# I-V_E9A_05_6231.net
KiCad netlist of a schematic drawn in Altium Designer
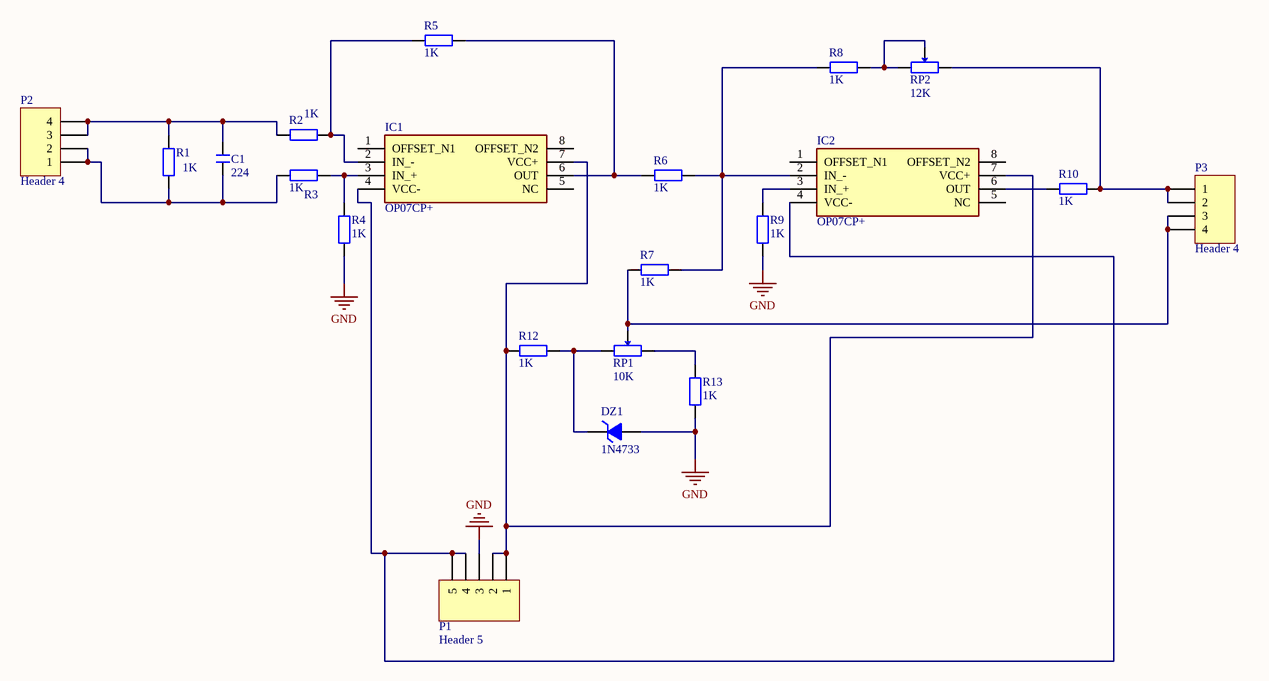
[diagram p0: I-V E9A_05_6231.SchDoc]

(export (version "E")
  (design (tool "Eeschema 10.0.6"))
  (components
    (comp (ref "C1")
      (value "224")
      (footprint "MLCC5.08-A")
      (description "独石电容")
      (fields (field (name "版权归属") "源创客"))
      (libsource (lib "3.1   - 电阻-电容-电感") (part "C-MLCC"))
    )
    (comp (ref "DZ1")
      (value "1N4733")
      (footprint "DO-41")
      (description "5.1V/1W稳压管")
      (fields (field (name "版权归属") "源创客"))
      (libsource (lib "8.1   - 二极管-整流桥") (part "1N4733"))
    )
    (comp (ref "IC1")
      (value "OP07CP+")
      (footprint "SamacSys:DIP794W53P254L959H508Q8N")
      (description "Integrated Circuit")
      (libsource (lib "*") (part "OP07CP+"))
    )
    (comp (ref "IC2")
      (value "OP07CP+")
      (footprint "SamacSys:DIP794W53P254L959H508Q8N")
      (description "Integrated Circuit")
      (libsource (lib "*") (part "OP07CP+"))
    )
    (comp (ref "P1")
      (value "Header 5")
      (footprint "POWER PLUG5")
      (description "Header, 5-Pin")
      (fields (field (name "PUBLISHER") "Altium Limited"))
      (libsource (lib "Miscellaneous Connectors") (part "Header 5"))
    )
    (comp (ref "P2")
      (value "Header 4")
      (footprint "HDR1X4")
      (description "Header, 4-Pin")
      (fields (field (name "PUBLISHER") "Altium Limited"))
      (libsource (lib "") (part "Header 4_1"))
    )
    (comp (ref "P3")
      (value "Header 4")
      (footprint "HDR1X4")
      (description "Header, 4-Pin")
      (fields (field (name "PUBLISHER") "Altium Limited"))
      (libsource (lib "Miscellaneous Connectors") (part "Header 4"))
    )
    (comp (ref "R1")
      (value "1K")
      (footprint "RS 1/4W")
      (description "直插色环电阻")
      (fields (field (name "版权归属") "源创客"))
      (libsource (lib "3.1   - 电阻-电容-电感") (part "R-CRR"))
    )
    (comp (ref "R2")
      (value "1K")
      (footprint "RS 1/4W")
      (description "直插色环电阻")
      (fields (field (name "版权归属") "源创客"))
      (libsource (lib "3.1   - 电阻-电容-电感") (part "R-CRR"))
    )
    (comp (ref "R3")
      (value "1K")
      (footprint "RS 1/4W")
      (description "直插色环电阻")
      (fields (field (name "版权归属") "源创客"))
      (libsource (lib "3.1   - 电阻-电容-电感") (part "R-CRR"))
    )
    (comp (ref "R4")
      (value "1K")
      (footprint "RS 1/4W")
      (description "直插色环电阻")
      (fields (field (name "版权归属") "源创客"))
      (libsource (lib "3.1   - 电阻-电容-电感") (part "R-CRR"))
    )
    (comp (ref "R5")
      (value "1K")
      (footprint "RS 1/4W")
      (description "直插色环电阻")
      (fields (field (name "版权归属") "源创客"))
      (libsource (lib "3.1   - 电阻-电容-电感") (part "R-CRR"))
    )
    (comp (ref "R6")
      (value "1K")
      (footprint "RS 1/4W")
      (description "直插色环电阻")
      (fields (field (name "版权归属") "源创客"))
      (libsource (lib "3.1   - 电阻-电容-电感") (part "R-CRR"))
    )
    (comp (ref "R7")
      (value "1K")
      (footprint "RS 1/4W")
      (description "直插色环电阻")
      (fields (field (name "版权归属") "源创客"))
      (libsource (lib "3.1   - 电阻-电容-电感") (part "R-CRR"))
    )
    (comp (ref "R8")
      (value "1K")
      (footprint "RS 1/4W")
      (description "直插色环电阻")
      (fields (field (name "版权归属") "源创客"))
      (libsource (lib "3.1   - 电阻-电容-电感") (part "R-CRR"))
    )
    (comp (ref "R9")
      (value "1K")
      (footprint "RS 1/4W")
      (description "直插色环电阻")
      (fields (field (name "版权归属") "源创客"))
      (libsource (lib "3.1   - 电阻-电容-电感") (part "R-CRR"))
    )
    (comp (ref "R10")
      (value "1K")
      (footprint "RS 1/4W")
      (description "直插色环电阻")
      (fields (field (name "版权归属") "源创客"))
      (libsource (lib "3.1   - 电阻-电容-电感") (part "R-CRR"))
    )
    (comp (ref "R12")
      (value "1K")
      (footprint "RS 1/4W")
      (description "直插色环电阻")
      (fields (field (name "版权归属") "源创客"))
      (libsource (lib "3.1   - 电阻-电容-电感") (part "R-CRR"))
    )
    (comp (ref "R13")
      (value "1K")
      (footprint "RS 1/4W")
      (description "直插色环电阻")
      (fields (field (name "版权归属") "源创客"))
      (libsource (lib "3.1   - 电阻-电容-电感") (part "R-CRR"))
    )
    (comp (ref "RP1")
      (value "10K")
      (footprint "3266Y")
      (description "插件单联电位器")
      (fields (field (name "版权归属") "源创客"))
      (libsource (lib "3.1   - 电阻-电容-电感") (part "RP-ID"))
    )
    (comp (ref "RP2")
      (value "12K")
      (footprint "3266Y")
      (description "插件单联电位器")
      (fields (field (name "版权归属") "源创客"))
      (libsource (lib "3.1   - 电阻-电容-电感") (part "RP-ID"))
    )
  )
  (nets
    (net (code "1") (name "GND") (class "Default")
      (node (ref "DZ1") (pin "1") (pinfunction "A_1") (pintype "passive"))
      (node (ref "P1") (pin "3") (pinfunction "3_3") (pintype "passive"))
      (node (ref "R13") (pin "1") (pinfunction "1_1") (pintype "passive"))
      (node (ref "R4") (pin "1") (pinfunction "1_1") (pintype "passive"))
      (node (ref "R9") (pin "1") (pinfunction "1_1") (pintype "passive"))
    )
    (net (code "2") (name "Net-(C1-Pad1)") (class "Default")
      (node (ref "C1") (pin "1") (pinfunction "1_1") (pintype "passive"))
      (node (ref "P2") (pin "1") (pinfunction "1_1") (pintype "passive"))
      (node (ref "P2") (pin "2") (pinfunction "2_2") (pintype "passive"))
      (node (ref "R1") (pin "1") (pinfunction "1_1") (pintype "passive"))
      (node (ref "R3") (pin "1") (pinfunction "1_1") (pintype "passive"))
    )
    (net (code "3") (name "Net-(C1-Pad2)") (class "Default")
      (node (ref "C1") (pin "2") (pinfunction "2_2") (pintype "passive"))
      (node (ref "P2") (pin "3") (pinfunction "3_3") (pintype "passive"))
      (node (ref "P2") (pin "4") (pinfunction "4_4") (pintype "passive"))
      (node (ref "R1") (pin "2") (pinfunction "2_2") (pintype "passive"))
      (node (ref "R2") (pin "1") (pinfunction "1_1") (pintype "passive"))
    )
    (net (code "4") (name "Net-(DZ1-K)") (class "Default")
      (node (ref "DZ1") (pin "2") (pinfunction "K_2") (pintype "passive"))
      (node (ref "R12") (pin "2") (pinfunction "2_2") (pintype "passive"))
      (node (ref "RP1") (pin "1") (pinfunction "1_1") (pintype "passive"))
    )
    (net (code "5") (name "Net-(IC1-IN_+)") (class "Default")
      (node (ref "IC1") (pin "3") (pinfunction "IN_+_3") (pintype "passive"))
      (node (ref "R3") (pin "2") (pinfunction "2_2") (pintype "passive"))
      (node (ref "R4") (pin "2") (pinfunction "2_2") (pintype "passive"))
    )
    (net (code "6") (name "Net-(IC1-IN_-)") (class "Default")
      (node (ref "IC1") (pin "2") (pinfunction "IN_-_2") (pintype "passive"))
      (node (ref "R2") (pin "2") (pinfunction "2_2") (pintype "passive"))
      (node (ref "R5") (pin "1") (pinfunction "1_1") (pintype "passive"))
    )
    (net (code "7") (name "Net-(IC1-OUT)") (class "Default")
      (node (ref "IC1") (pin "6") (pinfunction "OUT_6") (pintype "passive"))
      (node (ref "R5") (pin "2") (pinfunction "2_2") (pintype "passive"))
      (node (ref "R6") (pin "1") (pinfunction "1_1") (pintype "passive"))
    )
    (net (code "8") (name "Net-(IC1-VCC+)") (class "Default")
      (node (ref "IC1") (pin "7") (pinfunction "VCC+_7") (pintype "passive"))
      (node (ref "IC2") (pin "7") (pinfunction "VCC+_7") (pintype "passive"))
      (node (ref "P1") (pin "1") (pinfunction "1_1") (pintype "passive"))
      (node (ref "P1") (pin "2") (pinfunction "2_2") (pintype "passive"))
      (node (ref "R12") (pin "1") (pinfunction "1_1") (pintype "passive"))
    )
    (net (code "9") (name "Net-(IC1-VCC-)") (class "Default")
      (node (ref "IC1") (pin "4") (pinfunction "VCC-_4") (pintype "passive"))
      (node (ref "IC2") (pin "4") (pinfunction "VCC-_4") (pintype "passive"))
      (node (ref "P1") (pin "4") (pinfunction "4_4") (pintype "passive"))
      (node (ref "P1") (pin "5") (pinfunction "5_5") (pintype "passive"))
    )
    (net (code "10") (name "Net-(IC2-IN_+)") (class "Default")
      (node (ref "IC2") (pin "3") (pinfunction "IN_+_3") (pintype "passive"))
      (node (ref "R9") (pin "2") (pinfunction "2_2") (pintype "passive"))
    )
    (net (code "11") (name "Net-(IC2-IN_-)") (class "Default")
      (node (ref "IC2") (pin "2") (pinfunction "IN_-_2") (pintype "passive"))
      (node (ref "R6") (pin "2") (pinfunction "2_2") (pintype "passive"))
      (node (ref "R7") (pin "2") (pinfunction "2_2") (pintype "passive"))
      (node (ref "R8") (pin "1") (pinfunction "1_1") (pintype "passive"))
    )
    (net (code "12") (name "Net-(IC2-OUT)") (class "Default")
      (node (ref "IC2") (pin "6") (pinfunction "OUT_6") (pintype "passive"))
      (node (ref "R10") (pin "1") (pinfunction "1_1") (pintype "passive"))
    )
    (net (code "13") (name "Net-(P3-Pad1)") (class "Default")
      (node (ref "P3") (pin "1") (pinfunction "1_1") (pintype "passive"))
      (node (ref "P3") (pin "2") (pinfunction "2_2") (pintype "passive"))
      (node (ref "R10") (pin "2") (pinfunction "2_2") (pintype "passive"))
      (node (ref "RP2") (pin "3") (pinfunction "3_3") (pintype "passive"))
    )
    (net (code "14") (name "Net-(P3-Pad3)") (class "Default")
      (node (ref "P3") (pin "3") (pinfunction "3_3") (pintype "passive"))
      (node (ref "P3") (pin "4") (pinfunction "4_4") (pintype "passive"))
      (node (ref "R7") (pin "1") (pinfunction "1_1") (pintype "passive"))
      (node (ref "RP1") (pin "2") (pinfunction "2_2") (pintype "passive"))
    )
    (net (code "15") (name "Net-(R8-Pad2)") (class "Default")
      (node (ref "R8") (pin "2") (pinfunction "2_2") (pintype "passive"))
      (node (ref "RP2") (pin "1") (pinfunction "1_1") (pintype "passive"))
      (node (ref "RP2") (pin "2") (pinfunction "2_2") (pintype "passive"))
    )
    (net (code "16") (name "Net-(R13-Pad2)") (class "Default")
      (node (ref "R13") (pin "2") (pinfunction "2_2") (pintype "passive"))
      (node (ref "RP1") (pin "3") (pinfunction "3_3") (pintype "passive"))
    )
    (net (code "17") (name "unconnected-(IC1-NC-Pad5)") (class "Default")
      (node (ref "IC1") (pin "5") (pinfunction "NC_5") (pintype "passive"))
    )
    (net (code "18") (name "unconnected-(IC1-OFFSET_N1-Pad1)") (class "Default")
      (node (ref "IC1") (pin "1") (pinfunction "OFFSET_N1_1") (pintype "passive"))
    )
    (net (code "19") (name "unconnected-(IC1-OFFSET_N2-Pad8)") (class "Default")
      (node (ref "IC1") (pin "8") (pinfunction "OFFSET_N2_8") (pintype "passive"))
    )
    (net (code "20") (name "unconnected-(IC2-NC-Pad5)") (class "Default")
      (node (ref "IC2") (pin "5") (pinfunction "NC_5") (pintype "passive"))
    )
    (net (code "21") (name "unconnected-(IC2-OFFSET_N1-Pad1)") (class "Default")
      (node (ref "IC2") (pin "1") (pinfunction "OFFSET_N1_1") (pintype "passive"))
    )
    (net (code "22") (name "unconnected-(IC2-OFFSET_N2-Pad8)") (class "Default")
      (node (ref "IC2") (pin "8") (pinfunction "OFFSET_N2_8") (pintype "passive"))
    )
  )
)
